# SCH_555-circut_2025-03-21.net
KiCad netlist of a schematic drawn in EasyEDA
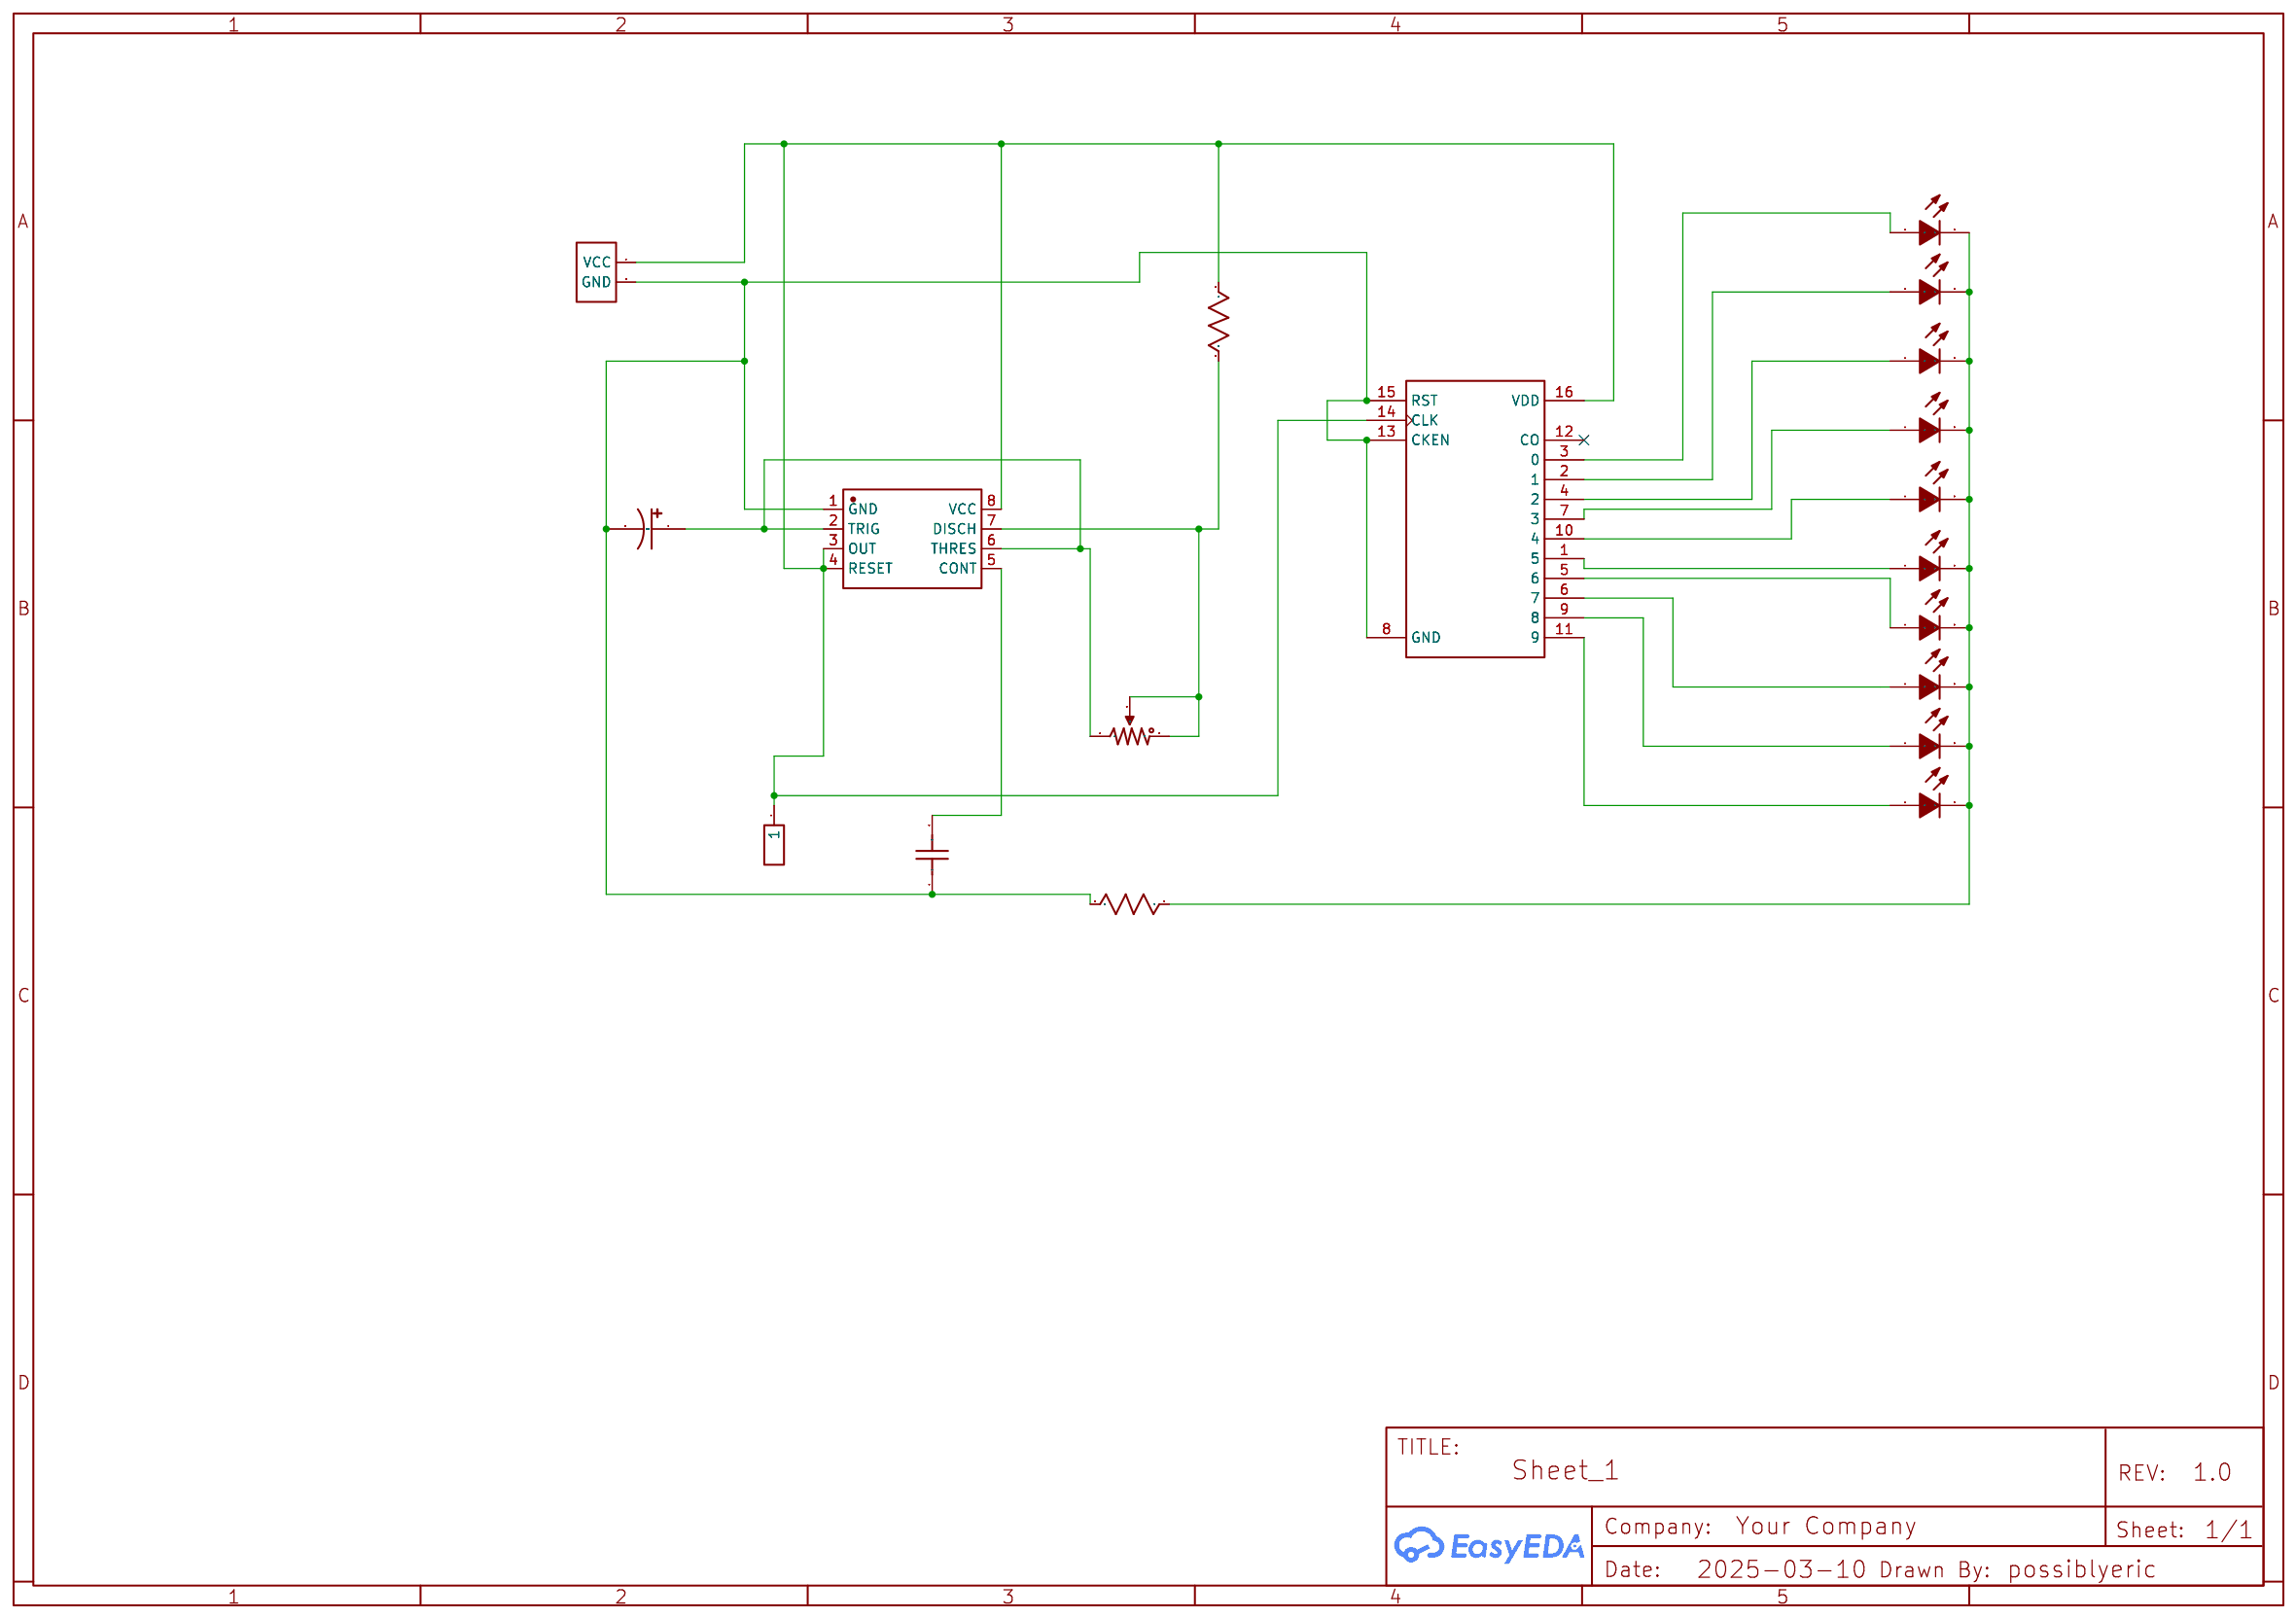
[diagram p0: schematic sheet]

(export (version "E")
  (design (tool "Eeschema 10.0.6"))
  (components
    (comp (ref "1") (value "LED_5MM") (libsource (lib "") (part "LED_5MM")))
    (comp (ref "2") (value "LED_5MM") (libsource (lib "") (part "LED_5MM")))
    (comp (ref "3") (value "LED_5MM") (libsource (lib "") (part "LED_5MM")))
    (comp (ref "4") (value "LED_5MM") (libsource (lib "") (part "LED_5MM")))
    (comp (ref "5") (value "LED_5MM") (libsource (lib "") (part "LED_5MM")))
    (comp (ref "6") (value "LED_5MM") (libsource (lib "") (part "LED_5MM")))
    (comp (ref "7") (value "LED_5MM") (libsource (lib "") (part "LED_5MM")))
    (comp (ref "8") (value "LED_5MM") (libsource (lib "") (part "LED_5MM")))
    (comp (ref "9") (value "LED_5MM") (libsource (lib "") (part "LED_5MM")))
    (comp (ref "10") (value "LED_5MM") (libsource (lib "") (part "LED_5MM")))
    (comp (ref "C1")
      (value "1uF")
      (fields (field (name "Manufacturer Part") "UVZ1H010MDD") (field (name "Manufacturer") "Nichicon(尼吉康)"))
      (libsource (lib "") (part "UVZ1H010MDD"))
    )
    (comp (ref "C2") (value "0.01u") (libsource (lib "") (part "C_0603_US")))
    (comp (ref "CLK1")
      (value "C81276")
      (fields
        (field (name "Manufacturer Part") "2.54-1*1P针")
        (field (name "Manufacturer") "BOOMELE(Boom Precision Elec)")
      )
      (libsource (lib "") (part "Header-Male-2.54_1x1"))
    )
    (comp (ref "H1") (value "Header") (libsource (lib "") (part "HEADER-FEMALE-2.54_1X2")))
    (comp (ref "R1")
      (value "470")
      (fields (field (name "Manufacturer Part") "?"))
      (libsource (lib "") (part "Resistor"))
    )
    (comp (ref "R2")
      (value "1k")
      (fields (field (name "Manufacturer Part") "?"))
      (libsource (lib "") (part "Resistor_1"))
    )
    (comp (ref "R4")
      (value "50k")
      (fields (field (name "Manufacturer Part") "?"))
      (libsource (lib "") (part "Potentiometer"))
    )
    (comp (ref "U2")
      (value "NE555P")
      (fields (field (name "Manufacturer") "TI(德州仪器)"))
      (libsource (lib "") (part "NE555P"))
    )
    (comp (ref "U4") (value "CD4017BCN") (libsource (lib "") (part "CD4017BCN")))
  )
  (nets
    (net (code "1") (name "Net-(1-A)") (class "Default")
      (node (ref "1") (pin "1") (pinfunction "A_1") (pintype "input"))
      (node (ref "U4") (pin "3") (pinfunction "0_3") (pintype "output"))
    )
    (net (code "2") (name "Net-(1-K)") (class "Default")
      (node (ref "1") (pin "2") (pinfunction "K_2") (pintype "input"))
      (node (ref "10") (pin "2") (pinfunction "K_2") (pintype "input"))
      (node (ref "2") (pin "2") (pinfunction "K_2") (pintype "input"))
      (node (ref "3") (pin "2") (pinfunction "K_2") (pintype "input"))
      (node (ref "4") (pin "2") (pinfunction "K_2") (pintype "input"))
      (node (ref "5") (pin "2") (pinfunction "K_2") (pintype "input"))
      (node (ref "6") (pin "2") (pinfunction "K_2") (pintype "input"))
      (node (ref "7") (pin "2") (pinfunction "K_2") (pintype "input"))
      (node (ref "8") (pin "2") (pinfunction "K_2") (pintype "input"))
      (node (ref "9") (pin "2") (pinfunction "K_2") (pintype "input"))
      (node (ref "R1") (pin "1") (pinfunction "1_1") (pintype "unspecified"))
    )
    (net (code "3") (name "Net-(2-A)") (class "Default")
      (node (ref "2") (pin "1") (pinfunction "A_1") (pintype "input"))
      (node (ref "U4") (pin "2") (pinfunction "1_2") (pintype "output"))
    )
    (net (code "4") (name "Net-(3-A)") (class "Default")
      (node (ref "3") (pin "1") (pinfunction "A_1") (pintype "input"))
      (node (ref "U4") (pin "4") (pinfunction "2_4") (pintype "output"))
    )
    (net (code "5") (name "Net-(4-A)") (class "Default")
      (node (ref "4") (pin "1") (pinfunction "A_1") (pintype "input"))
      (node (ref "U4") (pin "7") (pinfunction "3_7") (pintype "output"))
    )
    (net (code "6") (name "Net-(5-A)") (class "Default")
      (node (ref "5") (pin "1") (pinfunction "A_1") (pintype "input"))
      (node (ref "U4") (pin "10") (pinfunction "4_10") (pintype "output"))
    )
    (net (code "7") (name "Net-(6-A)") (class "Default")
      (node (ref "6") (pin "1") (pinfunction "A_1") (pintype "input"))
      (node (ref "U4") (pin "1") (pinfunction "5_1") (pintype "output"))
    )
    (net (code "8") (name "Net-(7-A)") (class "Default")
      (node (ref "7") (pin "1") (pinfunction "A_1") (pintype "input"))
      (node (ref "U4") (pin "5") (pinfunction "6_5") (pintype "output"))
    )
    (net (code "9") (name "Net-(8-A)") (class "Default")
      (node (ref "8") (pin "1") (pinfunction "A_1") (pintype "input"))
      (node (ref "U4") (pin "6") (pinfunction "7_6") (pintype "output"))
    )
    (net (code "10") (name "Net-(9-A)") (class "Default")
      (node (ref "9") (pin "1") (pinfunction "A_1") (pintype "input"))
      (node (ref "U4") (pin "9") (pinfunction "8_9") (pintype "output"))
    )
    (net (code "11") (name "Net-(10-A)") (class "Default")
      (node (ref "10") (pin "1") (pinfunction "A_1") (pintype "input"))
      (node (ref "U4") (pin "11") (pinfunction "9_11") (pintype "output"))
    )
    (net (code "12") (name "Net-(H1-GND)") (class "Default")
      (node (ref "C1") (pin "2") (pinfunction "2_2") (pintype "unspecified"))
      (node (ref "C2") (pin "1") (pinfunction "1_1") (pintype "unspecified"))
      (node (ref "H1") (pin "2") (pinfunction "GND_2") (pintype "unspecified"))
      (node (ref "R1") (pin "2") (pinfunction "2_2") (pintype "unspecified"))
      (node (ref "U2") (pin "1") (pinfunction "GND_1") (pintype "unspecified"))
      (node (ref "U4") (pin "13") (pinfunction "CKEN_13") (pintype "unspecified"))
      (node (ref "U4") (pin "15") (pinfunction "RST_15") (pintype "unspecified"))
      (node (ref "U4") (pin "8") (pinfunction "GND_8") (pintype "passive"))
    )
    (net (code "13") (name "Net-(H1-VCC)") (class "Default")
      (node (ref "CLK1") (pin "1") (pinfunction "1_1") (pintype "unspecified"))
      (node (ref "H1") (pin "1") (pinfunction "VCC_1") (pintype "unspecified"))
      (node (ref "R2") (pin "1") (pinfunction "1_1") (pintype "unspecified"))
      (node (ref "U2") (pin "3") (pinfunction "OUT_3") (pintype "unspecified"))
      (node (ref "U2") (pin "4") (pinfunction "RESET_4") (pintype "unspecified"))
      (node (ref "U2") (pin "8") (pinfunction "VCC_8") (pintype "unspecified"))
      (node (ref "U4") (pin "14") (pinfunction "CLK_14") (pintype "unspecified"))
      (node (ref "U4") (pin "16") (pinfunction "VDD_16") (pintype "passive"))
    )
    (net (code "14") (name "Net-(R4-2)") (class "Default")
      (node (ref "R2") (pin "2") (pinfunction "2_2") (pintype "unspecified"))
      (node (ref "R4") (pin "2") (pinfunction "3_2") (pintype "unspecified"))
      (node (ref "R4") (pin "3") (pinfunction "2_3") (pintype "unspecified"))
      (node (ref "U2") (pin "7") (pinfunction "DISCH_7") (pintype "unspecified"))
    )
    (net (code "15") (name "Net-(U2-CONT)") (class "Default")
      (node (ref "C2") (pin "2") (pinfunction "2_2") (pintype "unspecified"))
      (node (ref "U2") (pin "5") (pinfunction "CONT_5") (pintype "unspecified"))
    )
    (net (code "16") (name "Net-(U2-THRES)") (class "Default")
      (node (ref "C1") (pin "1") (pinfunction "1_1") (pintype "unspecified"))
      (node (ref "R4") (pin "1") (pinfunction "1_1") (pintype "unspecified"))
      (node (ref "U2") (pin "2") (pinfunction "TRIG_2") (pintype "unspecified"))
      (node (ref "U2") (pin "6") (pinfunction "THRES_6") (pintype "unspecified"))
    )
    (net (code "17") (name "unconnected-(U4-CO-Pad12)") (class "Default")
      (node (ref "U4") (pin "12") (pinfunction "CO_12") (pintype "output+no_connect"))
    )
  )
)
